# shiftregisterbuttons.net
KiCad netlist of a schematic drawn in EAGLE
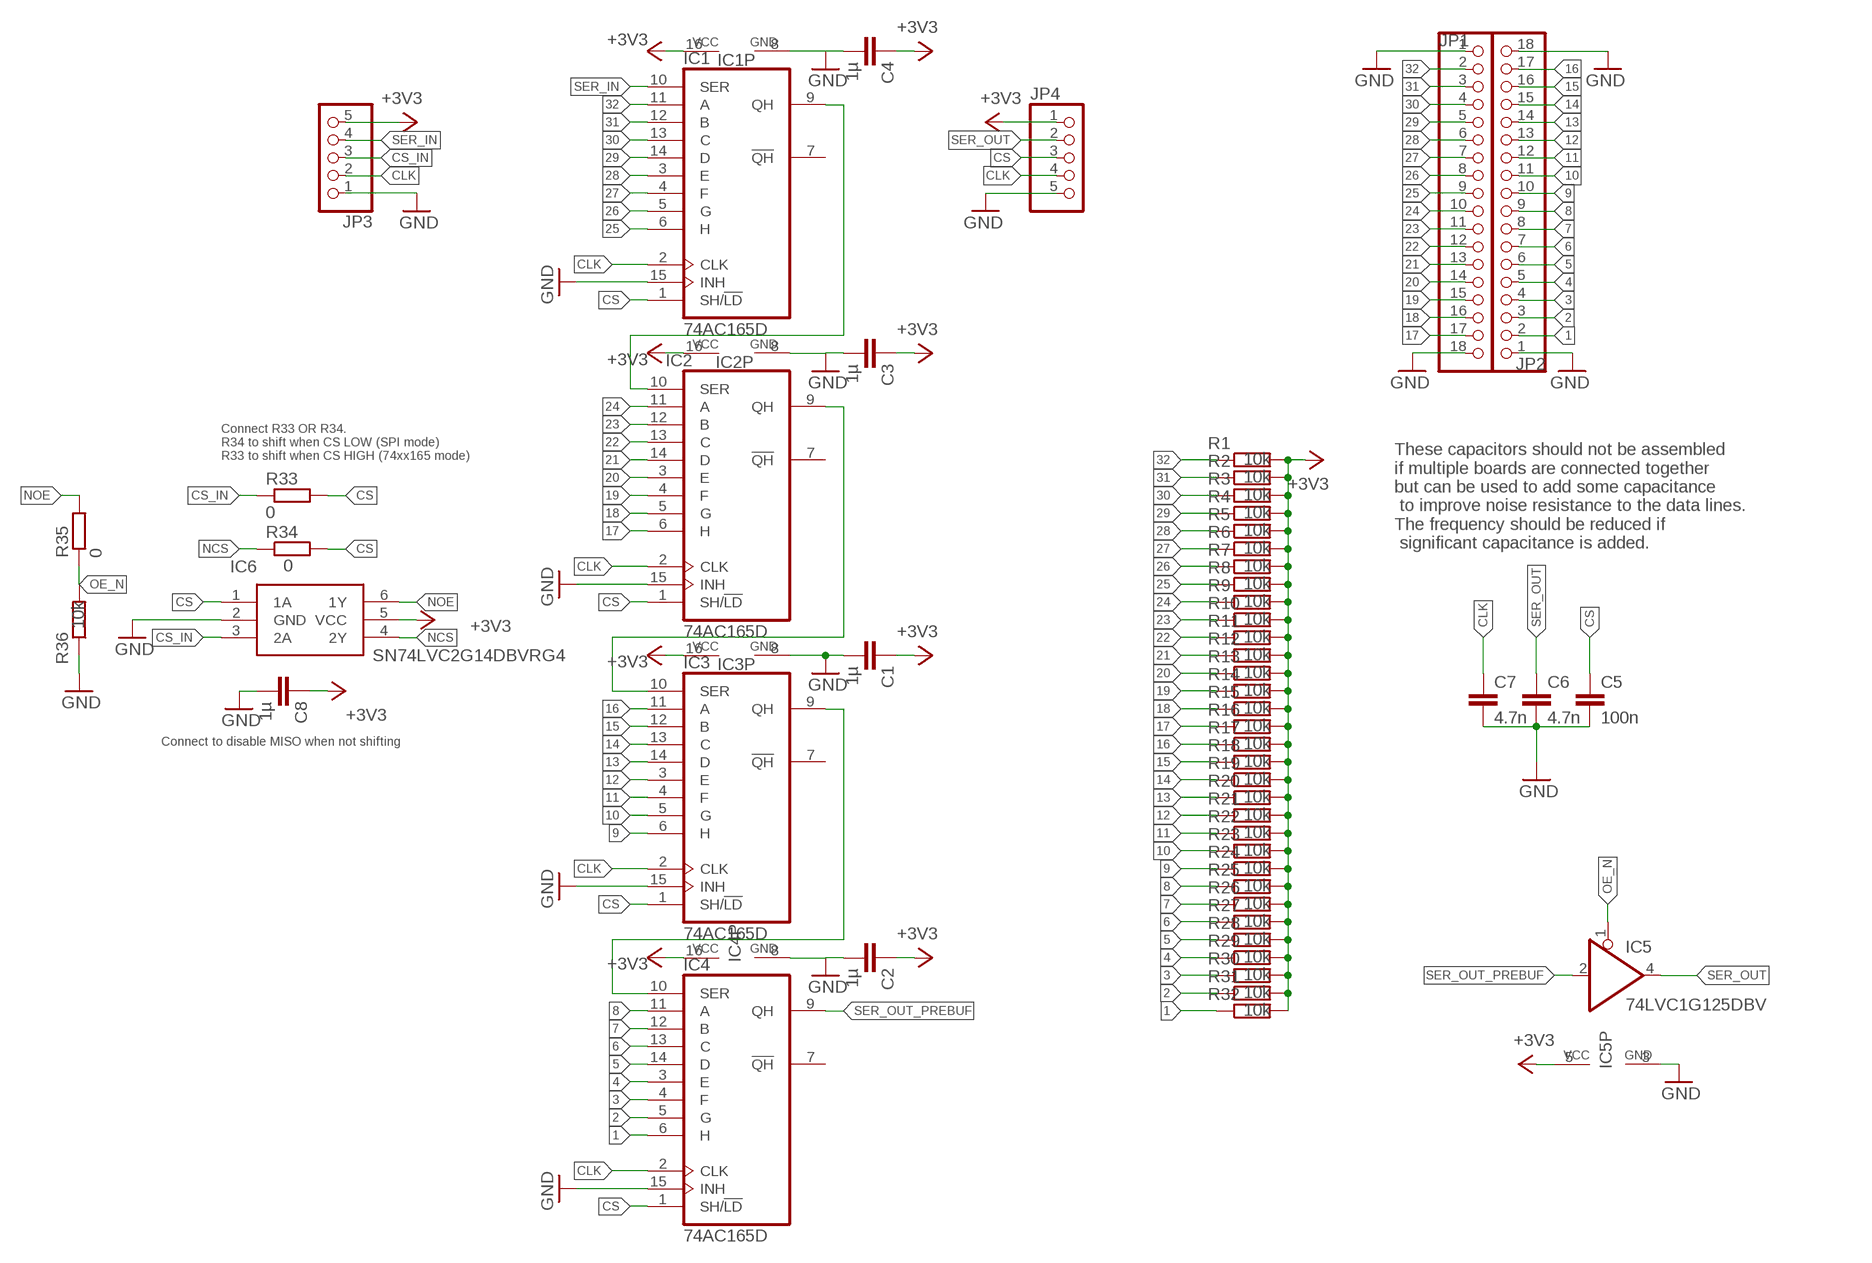
[diagram p0: schematic, sheet 1]

(export (version "E")
  (design (tool "Eeschema 10.0.6"))
  (components
    (comp (ref "C1")
      (value "1µ")
      (footprint "eagle-import:C0603")
      (libsource (lib "eagle-import") (part "C-EUC0603"))
    )
    (comp (ref "C2")
      (value "1µ")
      (footprint "eagle-import:C0603")
      (libsource (lib "eagle-import") (part "C-EUC0603"))
    )
    (comp (ref "C3")
      (value "1µ")
      (footprint "eagle-import:C0603")
      (libsource (lib "eagle-import") (part "C-EUC0603"))
    )
    (comp (ref "C4")
      (value "1µ")
      (footprint "eagle-import:C0603")
      (libsource (lib "eagle-import") (part "C-EUC0603"))
    )
    (comp (ref "C5")
      (value "100n")
      (footprint "eagle-import:C0603")
      (libsource (lib "eagle-import") (part "C-EUC0603"))
    )
    (comp (ref "C6")
      (value "4.7n")
      (footprint "eagle-import:C0603")
      (libsource (lib "eagle-import") (part "C-EUC0603"))
    )
    (comp (ref "C7")
      (value "4.7n")
      (footprint "eagle-import:C0603")
      (libsource (lib "eagle-import") (part "C-EUC0603"))
    )
    (comp (ref "C8")
      (value "1µ")
      (footprint "eagle-import:C0603")
      (libsource (lib "eagle-import") (part "C-EUC0603"))
    )
    (comp (ref "IC1")
      (value "74AC165D")
      (footprint "eagle-import:SO16")
      (libsource (lib "eagle-import") (part "74165DAC"))
    )
    (comp (ref "IC2")
      (value "74AC165D")
      (footprint "eagle-import:SO16")
      (libsource (lib "eagle-import") (part "74165DAC"))
    )
    (comp (ref "IC3")
      (value "74AC165D")
      (footprint "eagle-import:SO16")
      (libsource (lib "eagle-import") (part "74165DAC"))
    )
    (comp (ref "IC4")
      (value "74AC165D")
      (footprint "eagle-import:SO16")
      (libsource (lib "eagle-import") (part "74165DAC"))
    )
    (comp (ref "IC5")
      (value "74LVC1G125DBV")
      (footprint "eagle-import:SOT23-5")
      (libsource (lib "eagle-import") (part "741G125DBVLVC"))
    )
    (comp (ref "IC6")
      (value "SN74LVC2G14DBVRG4")
      (footprint "eagle-import:SOT95P280X145-6N")
      (fields (field (name "MOUSER_PART_NUMBER") "595-SN74LVC2G14DBVG4"))
      (libsource (lib "eagle-import") (part "SN74LVC2G14DBVRG4"))
    )
    (comp (ref "JP1")
      (value "PINHD-1X18")
      (footprint "eagle-import:1X18")
      (libsource (lib "eagle-import") (part "PINHD-1X18"))
    )
    (comp (ref "JP2")
      (value "PINHD-1X18")
      (footprint "eagle-import:1X18")
      (libsource (lib "eagle-import") (part "PINHD-1X18"))
    )
    (comp (ref "JP3")
      (value "PINHD-1X5")
      (footprint "eagle-import:1X05")
      (libsource (lib "eagle-import") (part "PINHD-1X5"))
    )
    (comp (ref "JP4")
      (value "PINHD-1X5")
      (footprint "eagle-import:1X05")
      (libsource (lib "eagle-import") (part "PINHD-1X5"))
    )
    (comp (ref "R1")
      (value "10k")
      (footprint "eagle-import:R0603")
      (libsource (lib "eagle-import") (part "R-EU_R0603"))
    )
    (comp (ref "R2")
      (value "10k")
      (footprint "eagle-import:R0603")
      (libsource (lib "eagle-import") (part "R-EU_R0603"))
    )
    (comp (ref "R3")
      (value "10k")
      (footprint "eagle-import:R0603")
      (libsource (lib "eagle-import") (part "R-EU_R0603"))
    )
    (comp (ref "R4")
      (value "10k")
      (footprint "eagle-import:R0603")
      (libsource (lib "eagle-import") (part "R-EU_R0603"))
    )
    (comp (ref "R5")
      (value "10k")
      (footprint "eagle-import:R0603")
      (libsource (lib "eagle-import") (part "R-EU_R0603"))
    )
    (comp (ref "R6")
      (value "10k")
      (footprint "eagle-import:R0603")
      (libsource (lib "eagle-import") (part "R-EU_R0603"))
    )
    (comp (ref "R7")
      (value "10k")
      (footprint "eagle-import:R0603")
      (libsource (lib "eagle-import") (part "R-EU_R0603"))
    )
    (comp (ref "R8")
      (value "10k")
      (footprint "eagle-import:R0603")
      (libsource (lib "eagle-import") (part "R-EU_R0603"))
    )
    (comp (ref "R9")
      (value "10k")
      (footprint "eagle-import:R0603")
      (libsource (lib "eagle-import") (part "R-EU_R0603"))
    )
    (comp (ref "R10")
      (value "10k")
      (footprint "eagle-import:R0603")
      (libsource (lib "eagle-import") (part "R-EU_R0603"))
    )
    (comp (ref "R11")
      (value "10k")
      (footprint "eagle-import:R0603")
      (libsource (lib "eagle-import") (part "R-EU_R0603"))
    )
    (comp (ref "R12")
      (value "10k")
      (footprint "eagle-import:R0603")
      (libsource (lib "eagle-import") (part "R-EU_R0603"))
    )
    (comp (ref "R13")
      (value "10k")
      (footprint "eagle-import:R0603")
      (libsource (lib "eagle-import") (part "R-EU_R0603"))
    )
    (comp (ref "R14")
      (value "10k")
      (footprint "eagle-import:R0603")
      (libsource (lib "eagle-import") (part "R-EU_R0603"))
    )
    (comp (ref "R15")
      (value "10k")
      (footprint "eagle-import:R0603")
      (libsource (lib "eagle-import") (part "R-EU_R0603"))
    )
    (comp (ref "R16")
      (value "10k")
      (footprint "eagle-import:R0603")
      (libsource (lib "eagle-import") (part "R-EU_R0603"))
    )
    (comp (ref "R17")
      (value "10k")
      (footprint "eagle-import:R0603")
      (libsource (lib "eagle-import") (part "R-EU_R0603"))
    )
    (comp (ref "R18")
      (value "10k")
      (footprint "eagle-import:R0603")
      (libsource (lib "eagle-import") (part "R-EU_R0603"))
    )
    (comp (ref "R19")
      (value "10k")
      (footprint "eagle-import:R0603")
      (libsource (lib "eagle-import") (part "R-EU_R0603"))
    )
    (comp (ref "R20")
      (value "10k")
      (footprint "eagle-import:R0603")
      (libsource (lib "eagle-import") (part "R-EU_R0603"))
    )
    (comp (ref "R21")
      (value "10k")
      (footprint "eagle-import:R0603")
      (libsource (lib "eagle-import") (part "R-EU_R0603"))
    )
    (comp (ref "R22")
      (value "10k")
      (footprint "eagle-import:R0603")
      (libsource (lib "eagle-import") (part "R-EU_R0603"))
    )
    (comp (ref "R23")
      (value "10k")
      (footprint "eagle-import:R0603")
      (libsource (lib "eagle-import") (part "R-EU_R0603"))
    )
    (comp (ref "R24")
      (value "10k")
      (footprint "eagle-import:R0603")
      (libsource (lib "eagle-import") (part "R-EU_R0603"))
    )
    (comp (ref "R25")
      (value "10k")
      (footprint "eagle-import:R0603")
      (libsource (lib "eagle-import") (part "R-EU_R0603"))
    )
    (comp (ref "R26")
      (value "10k")
      (footprint "eagle-import:R0603")
      (libsource (lib "eagle-import") (part "R-EU_R0603"))
    )
    (comp (ref "R27")
      (value "10k")
      (footprint "eagle-import:R0603")
      (libsource (lib "eagle-import") (part "R-EU_R0603"))
    )
    (comp (ref "R28")
      (value "10k")
      (footprint "eagle-import:R0603")
      (libsource (lib "eagle-import") (part "R-EU_R0603"))
    )
    (comp (ref "R29")
      (value "10k")
      (footprint "eagle-import:R0603")
      (libsource (lib "eagle-import") (part "R-EU_R0603"))
    )
    (comp (ref "R30")
      (value "10k")
      (footprint "eagle-import:R0603")
      (libsource (lib "eagle-import") (part "R-EU_R0603"))
    )
    (comp (ref "R31")
      (value "10k")
      (footprint "eagle-import:R0603")
      (libsource (lib "eagle-import") (part "R-EU_R0603"))
    )
    (comp (ref "R32")
      (value "10k")
      (footprint "eagle-import:R0603")
      (libsource (lib "eagle-import") (part "R-EU_R0603"))
    )
    (comp (ref "R33")
      (value "0")
      (footprint "eagle-import:R0603")
      (libsource (lib "eagle-import") (part "R-EU_R0603"))
    )
    (comp (ref "R34")
      (value "0")
      (footprint "eagle-import:R0603")
      (libsource (lib "eagle-import") (part "R-EU_R0603"))
    )
    (comp (ref "R35")
      (value "0")
      (footprint "eagle-import:R0603")
      (libsource (lib "eagle-import") (part "R-EU_R0603"))
    )
    (comp (ref "R36")
      (value "10k")
      (footprint "eagle-import:R0603")
      (libsource (lib "eagle-import") (part "R-EU_R0603"))
    )
  )
  (nets
    (net (code "1") (name "+3V3") (class "Default")
      (node (ref "C1") (pin "1") (pinfunction "1_1") (pintype "passive"))
      (node (ref "C2") (pin "1") (pinfunction "1_1") (pintype "passive"))
      (node (ref "C3") (pin "1") (pinfunction "1_1") (pintype "passive"))
      (node (ref "C4") (pin "1") (pinfunction "1_1") (pintype "passive"))
      (node (ref "C8") (pin "1") (pinfunction "1_1") (pintype "passive"))
      (node (ref "IC1") (pin "16") (pinfunction "VCC_16") (pintype "power_in"))
      (node (ref "IC2") (pin "16") (pinfunction "VCC_16") (pintype "power_in"))
      (node (ref "IC3") (pin "16") (pinfunction "VCC_16") (pintype "power_in"))
      (node (ref "IC4") (pin "16") (pinfunction "VCC_16") (pintype "power_in"))
      (node (ref "IC5") (pin "5") (pinfunction "VCC_5") (pintype "power_in"))
      (node (ref "IC6") (pin "5") (pinfunction "VCC_5") (pintype "bidirectional"))
      (node (ref "JP3") (pin "5") (pinfunction "5_5") (pintype "passive"))
      (node (ref "JP4") (pin "1") (pinfunction "1_1") (pintype "passive"))
      (node (ref "R1") (pin "2") (pinfunction "2_2") (pintype "passive"))
      (node (ref "R10") (pin "2") (pinfunction "2_2") (pintype "passive"))
      (node (ref "R11") (pin "2") (pinfunction "2_2") (pintype "passive"))
      (node (ref "R12") (pin "2") (pinfunction "2_2") (pintype "passive"))
      (node (ref "R13") (pin "2") (pinfunction "2_2") (pintype "passive"))
      (node (ref "R14") (pin "2") (pinfunction "2_2") (pintype "passive"))
      (node (ref "R15") (pin "2") (pinfunction "2_2") (pintype "passive"))
      (node (ref "R16") (pin "2") (pinfunction "2_2") (pintype "passive"))
      (node (ref "R17") (pin "2") (pinfunction "2_2") (pintype "passive"))
      (node (ref "R18") (pin "2") (pinfunction "2_2") (pintype "passive"))
      (node (ref "R19") (pin "2") (pinfunction "2_2") (pintype "passive"))
      (node (ref "R2") (pin "2") (pinfunction "2_2") (pintype "passive"))
      (node (ref "R20") (pin "2") (pinfunction "2_2") (pintype "passive"))
      (node (ref "R21") (pin "2") (pinfunction "2_2") (pintype "passive"))
      (node (ref "R22") (pin "2") (pinfunction "2_2") (pintype "passive"))
      (node (ref "R23") (pin "2") (pinfunction "2_2") (pintype "passive"))
      (node (ref "R24") (pin "2") (pinfunction "2_2") (pintype "passive"))
      (node (ref "R25") (pin "2") (pinfunction "2_2") (pintype "passive"))
      (node (ref "R26") (pin "2") (pinfunction "2_2") (pintype "passive"))
      (node (ref "R27") (pin "2") (pinfunction "2_2") (pintype "passive"))
      (node (ref "R28") (pin "2") (pinfunction "2_2") (pintype "passive"))
      (node (ref "R29") (pin "2") (pinfunction "2_2") (pintype "passive"))
      (node (ref "R3") (pin "2") (pinfunction "2_2") (pintype "passive"))
      (node (ref "R30") (pin "2") (pinfunction "2_2") (pintype "passive"))
      (node (ref "R31") (pin "2") (pinfunction "2_2") (pintype "passive"))
      (node (ref "R32") (pin "2") (pinfunction "2_2") (pintype "passive"))
      (node (ref "R4") (pin "2") (pinfunction "2_2") (pintype "passive"))
      (node (ref "R5") (pin "2") (pinfunction "2_2") (pintype "passive"))
      (node (ref "R6") (pin "2") (pinfunction "2_2") (pintype "passive"))
      (node (ref "R7") (pin "2") (pinfunction "2_2") (pintype "passive"))
      (node (ref "R8") (pin "2") (pinfunction "2_2") (pintype "passive"))
      (node (ref "R9") (pin "2") (pinfunction "2_2") (pintype "passive"))
    )
    (net (code "2") (name "1") (class "Default")
      (node (ref "IC4") (pin "6") (pinfunction "H_6") (pintype "input"))
      (node (ref "JP2") (pin "2") (pinfunction "2_2") (pintype "passive"))
      (node (ref "R32") (pin "1") (pinfunction "1_1") (pintype "passive"))
    )
    (net (code "3") (name "2") (class "Default")
      (node (ref "IC4") (pin "5") (pinfunction "G_5") (pintype "input"))
      (node (ref "JP2") (pin "3") (pinfunction "3_3") (pintype "passive"))
      (node (ref "R31") (pin "1") (pinfunction "1_1") (pintype "passive"))
    )
    (net (code "4") (name "3") (class "Default")
      (node (ref "IC4") (pin "4") (pinfunction "F_4") (pintype "input"))
      (node (ref "JP2") (pin "4") (pinfunction "4_4") (pintype "passive"))
      (node (ref "R30") (pin "1") (pinfunction "1_1") (pintype "passive"))
    )
    (net (code "5") (name "4") (class "Default")
      (node (ref "IC4") (pin "3") (pinfunction "E_3") (pintype "input"))
      (node (ref "JP2") (pin "5") (pinfunction "5_5") (pintype "passive"))
      (node (ref "R29") (pin "1") (pinfunction "1_1") (pintype "passive"))
    )
    (net (code "6") (name "5") (class "Default")
      (node (ref "IC4") (pin "14") (pinfunction "D_14") (pintype "input"))
      (node (ref "JP2") (pin "6") (pinfunction "6_6") (pintype "passive"))
      (node (ref "R28") (pin "1") (pinfunction "1_1") (pintype "passive"))
    )
    (net (code "7") (name "6") (class "Default")
      (node (ref "IC4") (pin "13") (pinfunction "C_13") (pintype "input"))
      (node (ref "JP2") (pin "7") (pinfunction "7_7") (pintype "passive"))
      (node (ref "R27") (pin "1") (pinfunction "1_1") (pintype "passive"))
    )
    (net (code "8") (name "7") (class "Default")
      (node (ref "IC4") (pin "12") (pinfunction "B_12") (pintype "input"))
      (node (ref "JP2") (pin "8") (pinfunction "8_8") (pintype "passive"))
      (node (ref "R26") (pin "1") (pinfunction "1_1") (pintype "passive"))
    )
    (net (code "9") (name "8") (class "Default")
      (node (ref "IC4") (pin "11") (pinfunction "A_11") (pintype "input"))
      (node (ref "JP2") (pin "9") (pinfunction "9_9") (pintype "passive"))
      (node (ref "R25") (pin "1") (pinfunction "1_1") (pintype "passive"))
    )
    (net (code "10") (name "9") (class "Default")
      (node (ref "IC3") (pin "6") (pinfunction "H_6") (pintype "input"))
      (node (ref "JP2") (pin "10") (pinfunction "10_10") (pintype "passive"))
      (node (ref "R24") (pin "1") (pinfunction "1_1") (pintype "passive"))
    )
    (net (code "11") (name "10") (class "Default")
      (node (ref "IC3") (pin "5") (pinfunction "G_5") (pintype "input"))
      (node (ref "JP2") (pin "11") (pinfunction "11_11") (pintype "passive"))
      (node (ref "R23") (pin "1") (pinfunction "1_1") (pintype "passive"))
    )
    (net (code "12") (name "11") (class "Default")
      (node (ref "IC3") (pin "4") (pinfunction "F_4") (pintype "input"))
      (node (ref "JP2") (pin "12") (pinfunction "12_12") (pintype "passive"))
      (node (ref "R22") (pin "1") (pinfunction "1_1") (pintype "passive"))
    )
    (net (code "13") (name "12") (class "Default")
      (node (ref "IC3") (pin "3") (pinfunction "E_3") (pintype "input"))
      (node (ref "JP2") (pin "13") (pinfunction "13_13") (pintype "passive"))
      (node (ref "R21") (pin "1") (pinfunction "1_1") (pintype "passive"))
    )
    (net (code "14") (name "13") (class "Default")
      (node (ref "IC3") (pin "14") (pinfunction "D_14") (pintype "input"))
      (node (ref "JP2") (pin "14") (pinfunction "14_14") (pintype "passive"))
      (node (ref "R20") (pin "1") (pinfunction "1_1") (pintype "passive"))
    )
    (net (code "15") (name "14") (class "Default")
      (node (ref "IC3") (pin "13") (pinfunction "C_13") (pintype "input"))
      (node (ref "JP2") (pin "15") (pinfunction "15_15") (pintype "passive"))
      (node (ref "R19") (pin "1") (pinfunction "1_1") (pintype "passive"))
    )
    (net (code "16") (name "15") (class "Default")
      (node (ref "IC3") (pin "12") (pinfunction "B_12") (pintype "input"))
      (node (ref "JP2") (pin "16") (pinfunction "16_16") (pintype "passive"))
      (node (ref "R18") (pin "1") (pinfunction "1_1") (pintype "passive"))
    )
    (net (code "17") (name "16") (class "Default")
      (node (ref "IC3") (pin "11") (pinfunction "A_11") (pintype "input"))
      (node (ref "JP2") (pin "17") (pinfunction "17_17") (pintype "passive"))
      (node (ref "R17") (pin "1") (pinfunction "1_1") (pintype "passive"))
    )
    (net (code "18") (name "17") (class "Default")
      (node (ref "IC2") (pin "6") (pinfunction "H_6") (pintype "input"))
      (node (ref "JP1") (pin "17") (pinfunction "17_17") (pintype "passive"))
      (node (ref "R16") (pin "1") (pinfunction "1_1") (pintype "passive"))
    )
    (net (code "19") (name "18") (class "Default")
      (node (ref "IC2") (pin "5") (pinfunction "G_5") (pintype "input"))
      (node (ref "JP1") (pin "16") (pinfunction "16_16") (pintype "passive"))
      (node (ref "R15") (pin "1") (pinfunction "1_1") (pintype "passive"))
    )
    (net (code "20") (name "19") (class "Default")
      (node (ref "IC2") (pin "4") (pinfunction "F_4") (pintype "input"))
      (node (ref "JP1") (pin "15") (pinfunction "15_15") (pintype "passive"))
      (node (ref "R14") (pin "1") (pinfunction "1_1") (pintype "passive"))
    )
    (net (code "21") (name "20") (class "Default")
      (node (ref "IC2") (pin "3") (pinfunction "E_3") (pintype "input"))
      (node (ref "JP1") (pin "14") (pinfunction "14_14") (pintype "passive"))
      (node (ref "R13") (pin "1") (pinfunction "1_1") (pintype "passive"))
    )
    (net (code "22") (name "21") (class "Default")
      (node (ref "IC2") (pin "14") (pinfunction "D_14") (pintype "input"))
      (node (ref "JP1") (pin "13") (pinfunction "13_13") (pintype "passive"))
      (node (ref "R12") (pin "1") (pinfunction "1_1") (pintype "passive"))
    )
    (net (code "23") (name "22") (class "Default")
      (node (ref "IC2") (pin "13") (pinfunction "C_13") (pintype "input"))
      (node (ref "JP1") (pin "12") (pinfunction "12_12") (pintype "passive"))
      (node (ref "R11") (pin "1") (pinfunction "1_1") (pintype "passive"))
    )
    (net (code "24") (name "23") (class "Default")
      (node (ref "IC2") (pin "12") (pinfunction "B_12") (pintype "input"))
      (node (ref "JP1") (pin "11") (pinfunction "11_11") (pintype "passive"))
      (node (ref "R10") (pin "1") (pinfunction "1_1") (pintype "passive"))
    )
    (net (code "25") (name "24") (class "Default")
      (node (ref "IC2") (pin "11") (pinfunction "A_11") (pintype "input"))
      (node (ref "JP1") (pin "10") (pinfunction "10_10") (pintype "passive"))
      (node (ref "R9") (pin "1") (pinfunction "1_1") (pintype "passive"))
    )
    (net (code "26") (name "25") (class "Default")
      (node (ref "IC1") (pin "6") (pinfunction "H_6") (pintype "input"))
      (node (ref "JP1") (pin "9") (pinfunction "9_9") (pintype "passive"))
      (node (ref "R8") (pin "1") (pinfunction "1_1") (pintype "passive"))
    )
    (net (code "27") (name "26") (class "Default")
      (node (ref "IC1") (pin "5") (pinfunction "G_5") (pintype "input"))
      (node (ref "JP1") (pin "8") (pinfunction "8_8") (pintype "passive"))
      (node (ref "R7") (pin "1") (pinfunction "1_1") (pintype "passive"))
    )
    (net (code "28") (name "27") (class "Default")
      (node (ref "IC1") (pin "4") (pinfunction "F_4") (pintype "input"))
      (node (ref "JP1") (pin "7") (pinfunction "7_7") (pintype "passive"))
      (node (ref "R6") (pin "1") (pinfunction "1_1") (pintype "passive"))
    )
    (net (code "29") (name "28") (class "Default")
      (node (ref "IC1") (pin "3") (pinfunction "E_3") (pintype "input"))
      (node (ref "JP1") (pin "6") (pinfunction "6_6") (pintype "passive"))
      (node (ref "R5") (pin "1") (pinfunction "1_1") (pintype "passive"))
    )
    (net (code "30") (name "29") (class "Default")
      (node (ref "IC1") (pin "14") (pinfunction "D_14") (pintype "input"))
      (node (ref "JP1") (pin "5") (pinfunction "5_5") (pintype "passive"))
      (node (ref "R4") (pin "1") (pinfunction "1_1") (pintype "passive"))
    )
    (net (code "31") (name "30") (class "Default")
      (node (ref "IC1") (pin "13") (pinfunction "C_13") (pintype "input"))
      (node (ref "JP1") (pin "4") (pinfunction "4_4") (pintype "passive"))
      (node (ref "R3") (pin "1") (pinfunction "1_1") (pintype "passive"))
    )
    (net (code "32") (name "31") (class "Default")
      (node (ref "IC1") (pin "12") (pinfunction "B_12") (pintype "input"))
      (node (ref "JP1") (pin "3") (pinfunction "3_3") (pintype "passive"))
      (node (ref "R2") (pin "1") (pinfunction "1_1") (pintype "passive"))
    )
    (net (code "33") (name "32") (class "Default")
      (node (ref "IC1") (pin "11") (pinfunction "A_11") (pintype "input"))
      (node (ref "JP1") (pin "2") (pinfunction "2_2") (pintype "passive"))
      (node (ref "R1") (pin "1") (pinfunction "1_1") (pintype "passive"))
    )
    (net (code "34") (name "CLK") (class "Default")
      (node (ref "C7") (pin "1") (pinfunction "1_1") (pintype "passive"))
      (node (ref "IC1") (pin "2") (pinfunction "CLK_2") (pintype "input"))
      (node (ref "IC2") (pin "2") (pinfunction "CLK_2") (pintype "input"))
      (node (ref "IC3") (pin "2") (pinfunction "CLK_2") (pintype "input"))
      (node (ref "IC4") (pin "2") (pinfunction "CLK_2") (pintype "input"))
      (node (ref "JP3") (pin "2") (pinfunction "2_2") (pintype "passive"))
      (node (ref "JP4") (pin "4") (pinfunction "4_4") (pintype "passive"))
    )
    (net (code "35") (name "CS") (class "Default")
      (node (ref "C5") (pin "1") (pinfunction "1_1") (pintype "passive"))
      (node (ref "IC1") (pin "1") (pinfunction "SH/~{LD}_1") (pintype "input"))
      (node (ref "IC2") (pin "1") (pinfunction "SH/~{LD}_1") (pintype "input"))
      (node (ref "IC3") (pin "1") (pinfunction "SH/~{LD}_1") (pintype "input"))
      (node (ref "IC4") (pin "1") (pinfunction "SH/~{LD}_1") (pintype "input"))
      (node (ref "IC6") (pin "1") (pinfunction "1A_1") (pintype "bidirectional"))
      (node (ref "JP4") (pin "3") (pinfunction "3_3") (pintype "passive"))
      (node (ref "R33") (pin "2") (pinfunction "2_2") (pintype "passive"))
      (node (ref "R34") (pin "2") (pinfunction "2_2") (pintype "passive"))
    )
    (net (code "36") (name "CS_IN") (class "Default")
      (node (ref "IC6") (pin "3") (pinfunction "2A_3") (pintype "bidirectional"))
      (node (ref "JP3") (pin "3") (pinfunction "3_3") (pintype "passive"))
      (node (ref "R33") (pin "1") (pinfunction "1_1") (pintype "passive"))
    )
    (net (code "37") (name "GND") (class "Default")
      (node (ref "C1") (pin "2") (pinfunction "2_2") (pintype "passive"))
      (node (ref "C2") (pin "2") (pinfunction "2_2") (pintype "passive"))
      (node (ref "C3") (pin "2") (pinfunction "2_2") (pintype "passive"))
      (node (ref "C4") (pin "2") (pinfunction "2_2") (pintype "passive"))
      (node (ref "C5") (pin "2") (pinfunction "2_2") (pintype "passive"))
      (node (ref "C6") (pin "2") (pinfunction "2_2") (pintype "passive"))
      (node (ref "C7") (pin "2") (pinfunction "2_2") (pintype "passive"))
      (node (ref "C8") (pin "2") (pinfunction "2_2") (pintype "passive"))
      (node (ref "IC1") (pin "15") (pinfunction "INH_15") (pintype "input"))
      (node (ref "IC1") (pin "8") (pinfunction "GND_8") (pintype "power_in"))
      (node (ref "IC2") (pin "15") (pinfunction "INH_15") (pintype "input"))
      (node (ref "IC2") (pin "8") (pinfunction "GND_8") (pintype "power_in"))
      (node (ref "IC3") (pin "15") (pinfunction "INH_15") (pintype "input"))
      (node (ref "IC3") (pin "8") (pinfunction "GND_8") (pintype "power_in"))
      (node (ref "IC4") (pin "15") (pinfunction "INH_15") (pintype "input"))
      (node (ref "IC4") (pin "8") (pinfunction "GND_8") (pintype "power_in"))
      (node (ref "IC5") (pin "3") (pinfunction "GND_3") (pintype "power_in"))
      (node (ref "IC6") (pin "2") (pinfunction "GND_2") (pintype "bidirectional"))
      (node (ref "JP1") (pin "1") (pinfunction "1_1") (pintype "passive"))
      (node (ref "JP1") (pin "18") (pinfunction "18_18") (pintype "passive"))
      (node (ref "JP2") (pin "1") (pinfunction "1_1") (pintype "passive"))
      (node (ref "JP2") (pin "18") (pinfunction "18_18") (pintype "passive"))
      (node (ref "JP3") (pin "1") (pinfunction "1_1") (pintype "passive"))
      (node (ref "JP4") (pin "5") (pinfunction "5_5") (pintype "passive"))
      (node (ref "R36") (pin "1") (pinfunction "1_1") (pintype "passive"))
    )
    (net (code "38") (name "NCS") (class "Default")
      (node (ref "IC6") (pin "4") (pinfunction "2Y_4") (pintype "bidirectional"))
      (node (ref "R34") (pin "1") (pinfunction "1_1") (pintype "passive"))
    )
    (net (code "39") (name "NOE") (class "Default")
      (node (ref "IC6") (pin "6") (pinfunction "1Y_6") (pintype "bidirectional"))
      (node (ref "R35") (pin "2") (pinfunction "2_2") (pintype "passive"))
    )
    (net (code "40") (name "Net-(IC1A-QH)") (class "Default")
      (node (ref "IC1") (pin "9") (pinfunction "QH_9") (pintype "output"))
      (node (ref "IC2") (pin "10") (pinfunction "SER_10") (pintype "input"))
    )
    (net (code "41") (name "Net-(IC2A-QH)") (class "Default")
      (node (ref "IC2") (pin "9") (pinfunction "QH_9") (pintype "output"))
      (node (ref "IC3") (pin "10") (pinfunction "SER_10") (pintype "input"))
    )
    (net (code "42") (name "Net-(IC3A-QH)") (class "Default")
      (node (ref "IC3") (pin "9") (pinfunction "QH_9") (pintype "output"))
      (node (ref "IC4") (pin "10") (pinfunction "SER_10") (pintype "input"))
    )
    (net (code "43") (name "OE_N") (class "Default")
      (node (ref "IC5") (pin "1") (pinfunction "OE_1") (pintype "input"))
      (node (ref "R35") (pin "1") (pinfunction "1_1") (pintype "passive"))
      (node (ref "R36") (pin "2") (pinfunction "2_2") (pintype "passive"))
    )
    (net (code "44") (name "SER_IN") (class "Default")
      (node (ref "IC1") (pin "10") (pinfunction "SER_10") (pintype "input"))
      (node (ref "JP3") (pin "4") (pinfunction "4_4") (pintype "passive"))
    )
    (net (code "45") (name "SER_OUT") (class "Default")
      (node (ref "C6") (pin "1") (pinfunction "1_1") (pintype "passive"))
      (node (ref "IC5") (pin "4") (pinfunction "O_4") (pintype "tri_state"))
      (node (ref "JP4") (pin "2") (pinfunction "2_2") (pintype "passive"))
    )
    (net (code "46") (name "SER_OUT_PREBUF") (class "Default")
      (node (ref "IC4") (pin "9") (pinfunction "QH_9") (pintype "output"))
      (node (ref "IC5") (pin "2") (pinfunction "I_2") (pintype "input"))
    )
    (net (code "47") (name "unconnected-(IC1A-~{QH}-Pad7)") (class "Default")
      (node (ref "IC1") (pin "7") (pinfunction "~{QH}_7") (pintype "output"))
    )
    (net (code "48") (name "unconnected-(IC2A-~{QH}-Pad7)") (class "Default")
      (node (ref "IC2") (pin "7") (pinfunction "~{QH}_7") (pintype "output"))
    )
    (net (code "49") (name "unconnected-(IC3A-~{QH}-Pad7)") (class "Default")
      (node (ref "IC3") (pin "7") (pinfunction "~{QH}_7") (pintype "output"))
    )
    (net (code "50") (name "unconnected-(IC4A-~{QH}-Pad7)") (class "Default")
      (node (ref "IC4") (pin "7") (pinfunction "~{QH}_7") (pintype "output"))
    )
  )
)
